# Power_3_3V_Rev1_1.net
KiCad netlist of a schematic drawn in Altium Designer
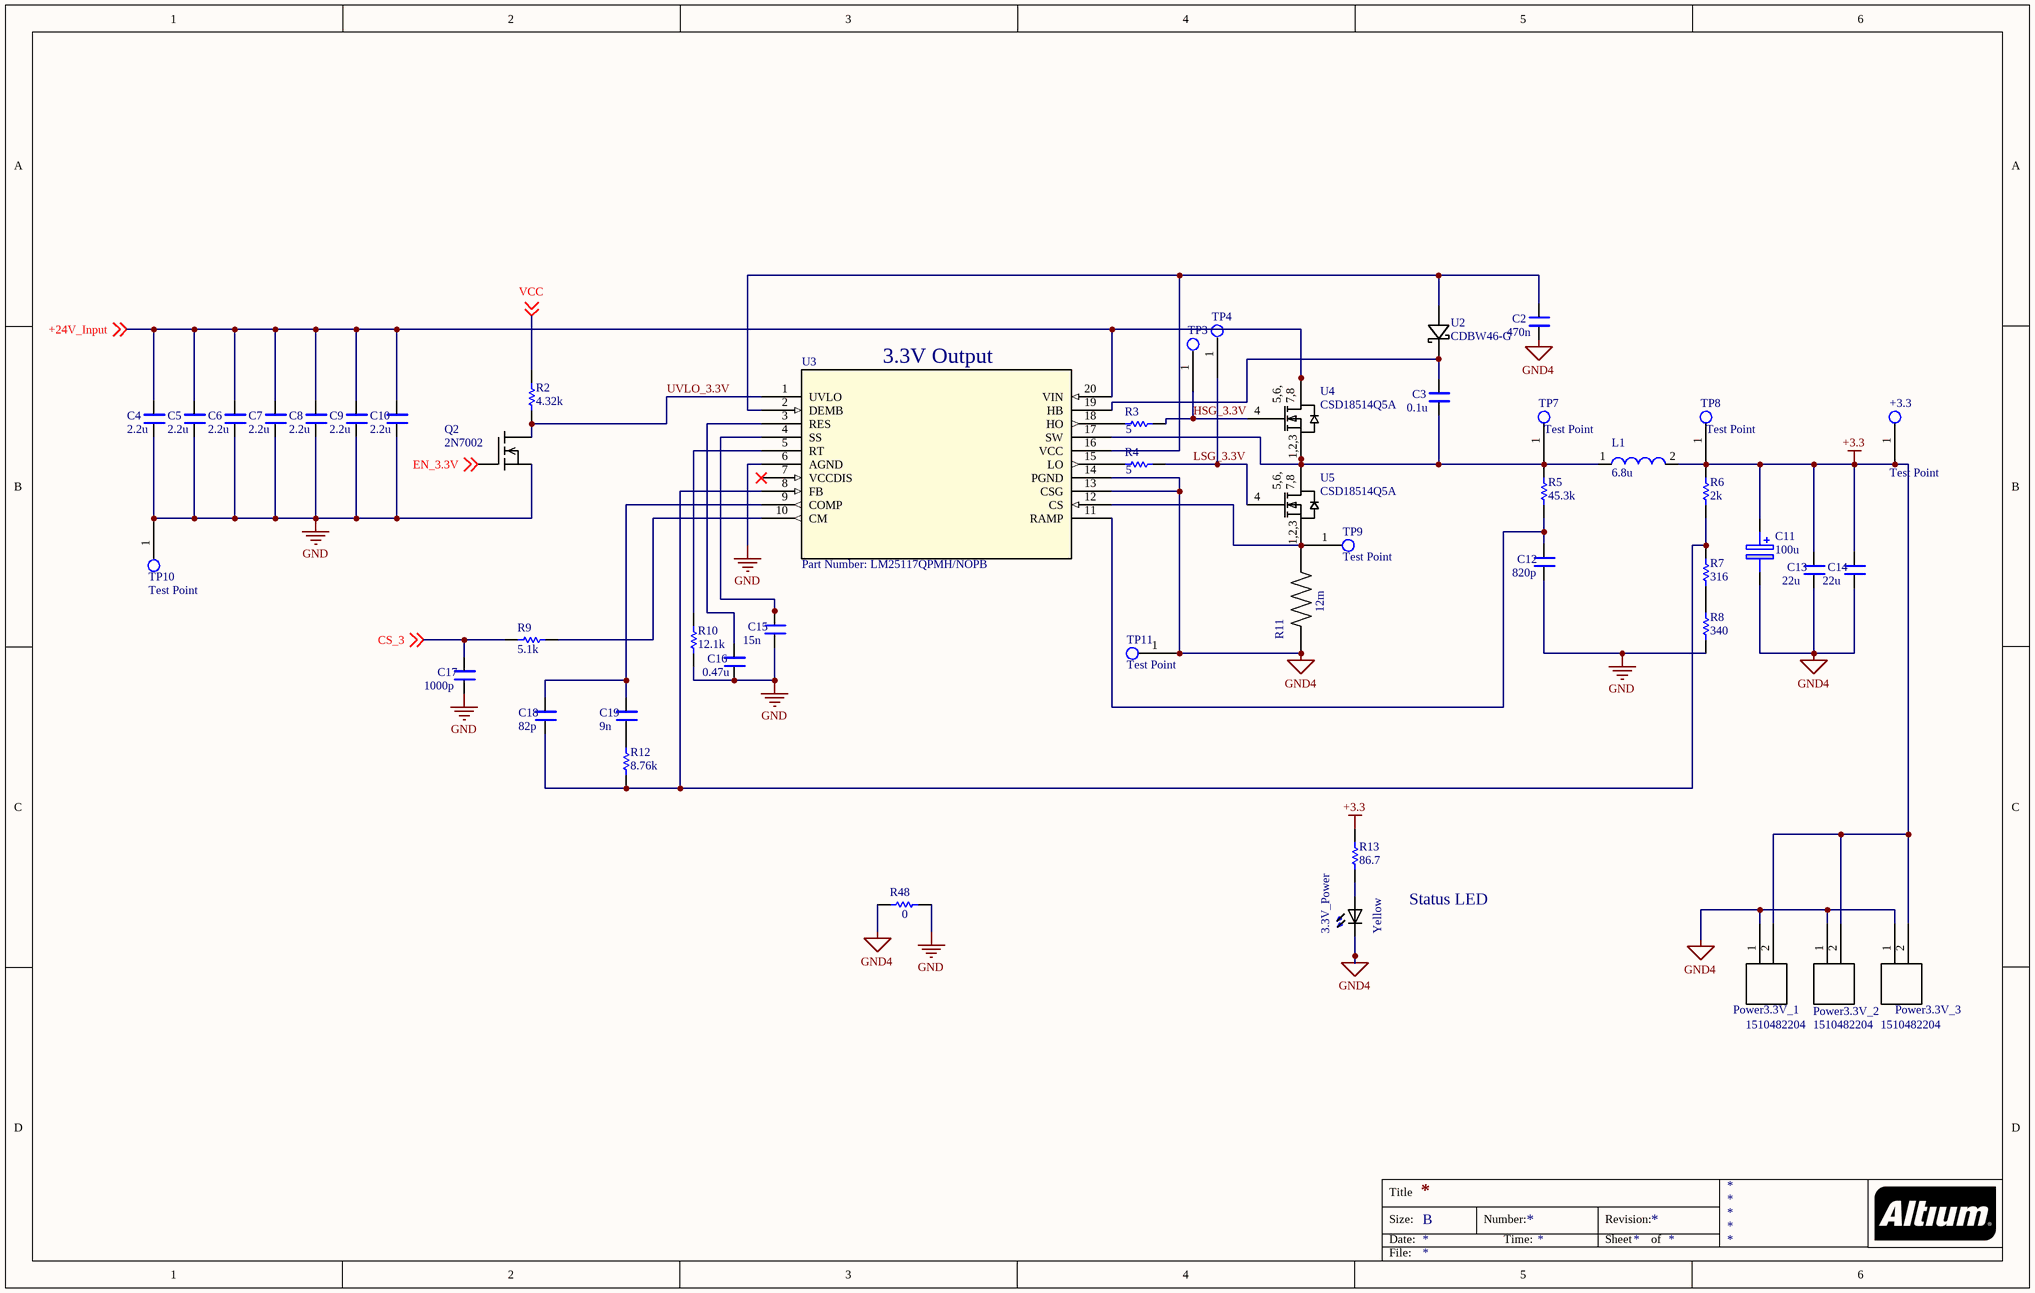
[diagram p0: Power_3.3V_Rev1.1.SchDoc]

(export (version "E")
  (design (tool "Eeschema 10.0.6"))
  (components
    (comp (ref "+3.3")
      (value "Test Point")
      (footprint "Test Point Through-hole")
      (libsource (lib "Test Points") (part "Test Point"))
    )
    (comp (ref "3.3V_Power")
      (value "Yellow")
      (footprint "*DIOC200X125X110_LTST-C171KSKT(Primary)")
      (description "Yellow 2 x 1.25 x 0.8 mm 130Â° Water Clear 50 mcd 2 V LED SMT")
      (fields (field (name "MP") "LTST-C171KSKT") (field (name "DIGI-KEY_PART_NUMBER") "160-1428-1-ND"))
      (libsource (lib "LTST-C171KSKT") (part "LTST-C171KSKT"))
    )
    (comp (ref "C2")
      (value "470n")
      (footprint "*CAPC2012X88N")
      (description "100pF Â±5% 250V Ceramic Capacitor C0G, NP0 0805 _2012 Metric_")
      (fields (field (name "MF") "KEMET") (field (name "DIGI-KEY_PART_NUMBER") "399-15000-1-ND"))
      (libsource (lib "C0805C101JAGAC7800") (part "C0805C101JAGAC7800"))
    )
    (comp (ref "C3")
      (value "0.1u")
      (footprint "*CAPC2012X88N")
      (description "100pF Â±5% 250V Ceramic Capacitor C0G, NP0 0805 _2012 Metric_")
      (fields (field (name "MF") "KEMET") (field (name "DIGI-KEY_PART_NUMBER") "399-15000-1-ND"))
      (libsource (lib "C0805C101JAGAC7800") (part "C0805C101JAGAC7800"))
    )
    (comp (ref "C4")
      (value "2.2u")
      (footprint "*CAPC2012X88N")
      (description "100pF Â±5% 250V Ceramic Capacitor C0G, NP0 0805 _2012 Metric_")
      (fields (field (name "MF") "KEMET") (field (name "DIGI-KEY_PART_NUMBER") "399-15000-1-ND"))
      (libsource (lib "C0805C101JAGAC7800") (part "C0805C101JAGAC7800"))
    )
    (comp (ref "C5")
      (value "2.2u")
      (footprint "*CAPC2012X88N")
      (description "100pF Â±5% 250V Ceramic Capacitor C0G, NP0 0805 _2012 Metric_")
      (fields (field (name "MF") "KEMET") (field (name "DIGI-KEY_PART_NUMBER") "399-15000-1-ND"))
      (libsource (lib "C0805C101JAGAC7800") (part "C0805C101JAGAC7800"))
    )
    (comp (ref "C6")
      (value "2.2u")
      (footprint "*CAPC2012X88N")
      (description "100pF Â±5% 250V Ceramic Capacitor C0G, NP0 0805 _2012 Metric_")
      (fields (field (name "MF") "KEMET") (field (name "DIGI-KEY_PART_NUMBER") "399-15000-1-ND"))
      (libsource (lib "C0805C101JAGAC7800") (part "C0805C101JAGAC7800"))
    )
    (comp (ref "C7")
      (value "2.2u")
      (footprint "*CAPC2012X88N")
      (description "100pF Â±5% 250V Ceramic Capacitor C0G, NP0 0805 _2012 Metric_")
      (fields (field (name "MF") "KEMET") (field (name "DIGI-KEY_PART_NUMBER") "399-15000-1-ND"))
      (libsource (lib "C0805C101JAGAC7800") (part "C0805C101JAGAC7800"))
    )
    (comp (ref "C8")
      (value "2.2u")
      (footprint "*CAPC2012X88N")
      (description "100pF Â±5% 250V Ceramic Capacitor C0G, NP0 0805 _2012 Metric_")
      (fields (field (name "MF") "KEMET") (field (name "DIGI-KEY_PART_NUMBER") "399-15000-1-ND"))
      (libsource (lib "C0805C101JAGAC7800") (part "C0805C101JAGAC7800"))
    )
    (comp (ref "C9")
      (value "2.2u")
      (footprint "*CAPC2012X88N")
      (description "100pF Â±5% 250V Ceramic Capacitor C0G, NP0 0805 _2012 Metric_")
      (fields (field (name "MF") "KEMET") (field (name "DIGI-KEY_PART_NUMBER") "399-15000-1-ND"))
      (libsource (lib "C0805C101JAGAC7800") (part "C0805C101JAGAC7800"))
    )
    (comp (ref "C10")
      (value "2.2u")
      (footprint "*CAPC2012X88N")
      (description "100pF Â±5% 250V Ceramic Capacitor C0G, NP0 0805 _2012 Metric_")
      (fields (field (name "MF") "KEMET") (field (name "DIGI-KEY_PART_NUMBER") "399-15000-1-ND"))
      (libsource (lib "C0805C101JAGAC7800") (part "C0805C101JAGAC7800"))
    )
    (comp (ref "C11")
      (value "100u")
      (footprint "CAPPRD500W65D1000H1800")
      (fields
        (field (name "MANUFACTURER_PART_NUMBER") "EEUFC1V331")
        (field (name "RS PART NUMBER") "1081337")
      )
      (libsource (lib "Power Distribution") (part "EEUFC1V331"))
    )
    (comp (ref "C12")
      (value "820p")
      (footprint "*CAPC2012X88N")
      (description "100pF Â±5% 250V Ceramic Capacitor C0G, NP0 0805 _2012 Metric_")
      (fields (field (name "MF") "KEMET") (field (name "DIGI-KEY_PART_NUMBER") "399-15000-1-ND"))
      (libsource (lib "C0805C101JAGAC7800") (part "C0805C101JAGAC7800"))
    )
    (comp (ref "C13")
      (value "22u")
      (footprint "*CAPC2012X88N")
      (description "100pF Â±5% 250V Ceramic Capacitor C0G, NP0 0805 _2012 Metric_")
      (fields (field (name "MF") "KEMET") (field (name "DIGI-KEY_PART_NUMBER") "399-15000-1-ND"))
      (libsource (lib "C0805C101JAGAC7800") (part "C0805C101JAGAC7800"))
    )
    (comp (ref "C14")
      (value "22u")
      (footprint "*CAPC2012X88N")
      (description "100pF Â±5% 250V Ceramic Capacitor C0G, NP0 0805 _2012 Metric_")
      (fields (field (name "MF") "KEMET") (field (name "DIGI-KEY_PART_NUMBER") "399-15000-1-ND"))
      (libsource (lib "C0805C101JAGAC7800") (part "C0805C101JAGAC7800"))
    )
    (comp (ref "C15")
      (value "15n")
      (footprint "*CAPC2012X88N")
      (description "100pF Â±5% 250V Ceramic Capacitor C0G, NP0 0805 _2012 Metric_")
      (fields (field (name "MF") "KEMET") (field (name "DIGI-KEY_PART_NUMBER") "399-15000-1-ND"))
      (libsource (lib "C0805C101JAGAC7800") (part "C0805C101JAGAC7800"))
    )
    (comp (ref "C16")
      (value "0.47u")
      (footprint "*CAPC2012X88N")
      (description "100pF Â±5% 250V Ceramic Capacitor C0G, NP0 0805 _2012 Metric_")
      (fields (field (name "MF") "KEMET") (field (name "DIGI-KEY_PART_NUMBER") "399-15000-1-ND"))
      (libsource (lib "C0805C101JAGAC7800") (part "C0805C101JAGAC7800"))
    )
    (comp (ref "C17")
      (value "1000p")
      (footprint "*CAPC2012X88N")
      (description "100pF Â±5% 250V Ceramic Capacitor C0G, NP0 0805 _2012 Metric_")
      (fields (field (name "MF") "KEMET") (field (name "DIGI-KEY_PART_NUMBER") "399-15000-1-ND"))
      (libsource (lib "C0805C101JAGAC7800") (part "C0805C101JAGAC7800"))
    )
    (comp (ref "C18")
      (value "82p")
      (footprint "*CAPC2012X88N")
      (description "100pF Â±5% 250V Ceramic Capacitor C0G, NP0 0805 _2012 Metric_")
      (fields (field (name "MF") "KEMET") (field (name "DIGI-KEY_PART_NUMBER") "399-15000-1-ND"))
      (libsource (lib "C0805C101JAGAC7800") (part "C0805C101JAGAC7800"))
    )
    (comp (ref "C19")
      (value "9n")
      (footprint "*CAPC2012X88N")
      (description "100pF Â±5% 250V Ceramic Capacitor C0G, NP0 0805 _2012 Metric_")
      (fields (field (name "MF") "KEMET") (field (name "DIGI-KEY_PART_NUMBER") "399-15000-1-ND"))
      (libsource (lib "C0805C101JAGAC7800") (part "C0805C101JAGAC7800"))
    )
    (comp (ref "L1")
      (value "6.8u")
      (footprint "XAL1010-682")
      (description "Power inductor, high current, 10% tol, SMT, RoHS")
      (fields (field (name "MF") "Coilcraft") (field (name "MP") "SER2915H-153KL"))
      (libsource (lib "SER2915H-153KL") (part "SER2915H-153KL"))
    )
    (comp (ref "Power3.3V_1")
      (value "1510482204")
      (footprint "1510482204")
      (description "Molex 6.5MM 2 pin connector, used for power connections. P/N 1510482204 and similar models.")
      (libsource (lib "Power Distribution") (part "1510482204"))
    )
    (comp (ref "Power3.3V_2")
      (value "1510482204")
      (footprint "1510482204")
      (description "Molex 6.5MM 2 pin connector, used for power connections. P/N 1510482204 and similar models.")
      (libsource (lib "Power Distribution") (part "1510482204"))
    )
    (comp (ref "Power3.3V_3")
      (value "1510482204")
      (footprint "1510482204")
      (description "Molex 6.5MM 2 pin connector, used for power connections. P/N 1510482204 and similar models.")
      (libsource (lib "Power Distribution") (part "1510482204"))
    )
    (comp (ref "Q2")
      (value "2N7002")
      (footprint "*SOT23")
      (description "Trans MOSFET N-CH 60V 0.115A 3-Pin SOT-23 T/R")
      (fields (field (name "MF") "ON Semiconductor"))
      (libsource (lib "2N7002") (part "2N7002"))
    )
    (comp (ref "R2")
      (value "4.32k")
      (footprint "RESC0805(2012)_M")
      (description "8M06 0.125W 1% 0805 (2012 Metric)  SMD")
      (fields (field (name "POWER") "0.125 W") (field (name "TOLERANCE") "1 %"))
      (libsource (lib "Altium Content Vault") (part "RES"))
    )
    (comp (ref "R3")
      (value "5")
      (footprint "AXIAL-0.3")
      (description "120R 0.125W 5% 0805 (2012 Metric)  SMD")
      (fields (field (name "TOLERANCE") "5 %") (field (name "POWER") "0.125 W"))
      (libsource (lib "Power Distribution") (part "120R 5% 0805"))
    )
    (comp (ref "R4")
      (value "5")
      (footprint "AXIAL-0.3")
      (description "120R 0.125W 5% 0805 (2012 Metric)  SMD")
      (fields (field (name "TOLERANCE") "5 %") (field (name "POWER") "0.125 W"))
      (libsource (lib "Power Distribution") (part "120R 5% 0805"))
    )
    (comp (ref "R5")
      (value "45.3k")
      (footprint "RESC0805(2012)_M")
      (description "8M06 0.125W 1% 0805 (2012 Metric)  SMD")
      (fields (field (name "POWER") "0.125 W") (field (name "TOLERANCE") "1 %"))
      (libsource (lib "Altium Content Vault") (part "RES"))
    )
    (comp (ref "R6")
      (value "2k")
      (footprint "RESC0805(2012)_M")
      (description "8M06 0.125W 1% 0805 (2012 Metric)  SMD")
      (fields (field (name "POWER") "0.125 W") (field (name "TOLERANCE") "1 %"))
      (libsource (lib "Altium Content Vault") (part "RES"))
    )
    (comp (ref "R7")
      (value "316")
      (footprint "RESC0805(2012)_M")
      (description "8M06 0.125W 1% 0805 (2012 Metric)  SMD")
      (fields (field (name "POWER") "0.125 W") (field (name "TOLERANCE") "1 %"))
      (libsource (lib "Altium Content Vault") (part "RES"))
    )
    (comp (ref "R8")
      (value "340")
      (footprint "RESC0805(2012)_M")
      (description "8M06 0.125W 1% 0805 (2012 Metric)  SMD")
      (fields (field (name "POWER") "0.125 W") (field (name "TOLERANCE") "1 %"))
      (libsource (lib "Altium Content Vault") (part "RES"))
    )
    (comp (ref "R9")
      (value "5.1k")
      (footprint "RESC0805(2012)_M")
      (description "8M06 0.125W 1% 0805 (2012 Metric)  SMD")
      (fields (field (name "POWER") "0.125 W") (field (name "TOLERANCE") "1 %"))
      (libsource (lib "Altium Content Vault") (part "RES"))
    )
    (comp (ref "R10")
      (value "12.1k")
      (footprint "RESC0805(2012)_M")
      (description "8M06 0.125W 1% 0805 (2012 Metric)  SMD")
      (fields (field (name "POWER") "0.125 W") (field (name "TOLERANCE") "1 %"))
      (libsource (lib "Altium Content Vault") (part "RES"))
    )
    (comp (ref "R11")
      (value "12m")
      (footprint "*RESC6432X110N")
      (description "Res Thick Film 2512 0.012 Ohm 1% 1W Pad SMD Automotive T/R")
      (fields (field (name "MP") "ERJ-M1WSF12MU") (field (name "DIGI-KEY_PART_NUMBER") "P12MCT-ND"))
      (libsource (lib "ERJ-M1WSF12MU") (part "ERJ-M1WSF12MU"))
    )
    (comp (ref "R12")
      (value "8.76k")
      (footprint "RESC0805(2012)_M")
      (description "8M06 0.125W 1% 0805 (2012 Metric)  SMD")
      (fields (field (name "POWER") "0.125 W") (field (name "TOLERANCE") "1 %"))
      (libsource (lib "Altium Content Vault") (part "RES"))
    )
    (comp (ref "R13")
      (value "86.7")
      (footprint "RESC0805(2012)_M")
      (description "8M06 0.125W 1% 0805 (2012 Metric)  SMD")
      (fields (field (name "POWER") "0.125 W") (field (name "TOLERANCE") "1 %"))
      (libsource (lib "Altium Content Vault") (part "RES"))
    )
    (comp (ref "R48")
      (value "0")
      (footprint "RESC0805(2012)_M")
      (description "8M06 0.125W 1% 0805 (2012 Metric)  SMD")
      (fields (field (name "POWER") "0.125 W") (field (name "TOLERANCE") "1 %"))
      (libsource (lib "Altium Content Vault") (part "RES"))
    )
    (comp (ref "TP3")
      (value "~")
      (footprint "Test Point Through-hole")
      (libsource (lib "Test Points") (part "Test Point"))
    )
    (comp (ref "TP4")
      (value "~")
      (footprint "Test Point Through-hole")
      (libsource (lib "Test Points") (part "Test Point"))
    )
    (comp (ref "TP7")
      (value "Test Point")
      (footprint "Test Point Through-hole")
      (libsource (lib "Test Points") (part "Test Point"))
    )
    (comp (ref "TP8")
      (value "Test Point")
      (footprint "Test Point Through-hole")
      (libsource (lib "Test Points") (part "Test Point"))
    )
    (comp (ref "TP9")
      (value "Test Point")
      (footprint "Test Point Through-hole")
      (libsource (lib "Test Points") (part "Test Point"))
    )
    (comp (ref "TP10")
      (value "Test Point")
      (footprint "Test Point Through-hole")
      (libsource (lib "Test Points") (part "Test Point"))
    )
    (comp (ref "TP11")
      (value "Test Point")
      (footprint "Test Point Through-hole")
      (libsource (lib "Test Points") (part "Test Point"))
    )
    (comp (ref "U2")
      (value "CDBW46-G")
      (footprint "CDBW")
      (description "No Description Available")
      (fields (field (name "COPYRIGHT") "Copyright (C) 2018 Accelerated Designs. All rights reserved"))
      (libsource (lib "DIODE SCHOTTKY 100V 150MA") (part "CDBW46-G"))
    )
    (comp (ref "U3")
      (value "Part Number: LM25117QPMH/NOPB")
      (footprint "MXA20A")
      (description "No Description Available")
      (fields
        (field (name "MANUFACTURER") "Texas Instruments")
        (field (name "MANUFACTURER_PART_NUMBER") "LM25117QPMH/NOPB")
        (field (name "COPYRIGHT") "Copyright (C) 2018 Accelerated Designs. All rights reserved")
      )
      (libsource (lib "2019-11-16_22-35-15") (part "LM25117QPMH/NOPB"))
    )
    (comp (ref "U4")
      (value "CSD18514Q5A")
      (footprint "DQJ0008A")
      (description "No Description Available")
      (fields (field (name "COPYRIGHT") "Copyright (C) 2018 Accelerated Designs. All rights reserved"))
      (libsource (lib "ul_CSD18514Q5A") (part "CSD18514Q5A"))
    )
    (comp (ref "U5")
      (value "CSD18514Q5A")
      (footprint "DQJ0008A")
      (description "No Description Available")
      (fields (field (name "COPYRIGHT") "Copyright (C) 2018 Accelerated Designs. All rights reserved"))
      (libsource (lib "ul_CSD18514Q5A") (part "CSD18514Q5A"))
    )
  )
  (nets
    (net (code "1") (name "+3.3") (class "Default")
      (node (ref "+3.3") (pin "1") (pinfunction "1_1") (pintype "passive"))
      (node (ref "C11") (pin "1") (pinfunction "+_1") (pintype "passive"))
      (node (ref "C13") (pin "2") (pinfunction "2_2") (pintype "passive"))
      (node (ref "C14") (pin "2") (pinfunction "2_2") (pintype "passive"))
      (node (ref "L1") (pin "2") (pinfunction "2_2") (pintype "passive"))
      (node (ref "Power3.3V_1") (pin "2") (pintype "passive"))
      (node (ref "Power3.3V_2") (pin "2") (pintype "passive"))
      (node (ref "Power3.3V_3") (pin "2") (pintype "passive"))
      (node (ref "R13") (pin "2") (pinfunction "2_2") (pintype "passive"))
      (node (ref "R6") (pin "2") (pinfunction "2_2") (pintype "passive"))
      (node (ref "TP8") (pin "1") (pinfunction "1_1") (pintype "passive"))
    )
    (net (code "2") (name "+24V_Input") (class "Default")
      (node (ref "C10") (pin "2") (pinfunction "2_2") (pintype "passive"))
      (node (ref "C4") (pin "2") (pinfunction "2_2") (pintype "passive"))
      (node (ref "C5") (pin "2") (pinfunction "2_2") (pintype "passive"))
      (node (ref "C6") (pin "2") (pinfunction "2_2") (pintype "passive"))
      (node (ref "C7") (pin "2") (pinfunction "2_2") (pintype "passive"))
      (node (ref "C8") (pin "2") (pinfunction "2_2") (pintype "passive"))
      (node (ref "C9") (pin "2") (pinfunction "2_2") (pintype "passive"))
      (node (ref "U3") (pin "20") (pinfunction "VIN_20") (pintype "input"))
      (node (ref "U4") (pin "5") (pinfunction "D_5") (pintype "passive"))
      (node (ref "U4") (pin "6") (pinfunction "D_6") (pintype "passive"))
      (node (ref "U4") (pin "7") (pinfunction "D_7") (pintype "passive"))
      (node (ref "U4") (pin "8") (pinfunction "D_8") (pintype "passive"))
    )
    (net (code "3") (name "/HSG_3.3V") (class "Default")
      (node (ref "R3") (pin "2") (pinfunction "2_2") (pintype "passive"))
      (node (ref "TP3") (pin "1") (pinfunction "1_1") (pintype "passive"))
      (node (ref "U4") (pin "4") (pinfunction "G_4") (pintype "passive"))
    )
    (net (code "4") (name "/LSG_3.3V") (class "Default")
      (node (ref "R4") (pin "2") (pinfunction "2_2") (pintype "passive"))
      (node (ref "TP4") (pin "1") (pinfunction "1_1") (pintype "passive"))
      (node (ref "U5") (pin "4") (pinfunction "G_4") (pintype "passive"))
    )
    (net (code "5") (name "/UVLO_3.3V") (class "Default")
      (node (ref "Q2") (pin "3") (pinfunction "D_3") (pintype "passive"))
      (node (ref "R2") (pin "1") (pinfunction "1_1") (pintype "passive"))
      (node (ref "U3") (pin "1") (pinfunction "UVLO_1") (pintype "passive"))
    )
    (net (code "6") (name "CS_3") (class "Default")
      (node (ref "C17") (pin "2") (pinfunction "2_2") (pintype "passive"))
      (node (ref "R9") (pin "2") (pinfunction "2_2") (pintype "passive"))
    )
    (net (code "7") (name "EN_3.3V") (class "Default")
      (node (ref "Q2") (pin "1") (pinfunction "G_1") (pintype "passive"))
    )
    (net (code "8") (name "GND") (class "Default")
      (node (ref "C10") (pin "1") (pinfunction "1_1") (pintype "passive"))
      (node (ref "C12") (pin "1") (pinfunction "1_1") (pintype "passive"))
      (node (ref "C15") (pin "1") (pinfunction "1_1") (pintype "passive"))
      (node (ref "C16") (pin "1") (pinfunction "1_1") (pintype "passive"))
      (node (ref "C17") (pin "1") (pinfunction "1_1") (pintype "passive"))
      (node (ref "C4") (pin "1") (pinfunction "1_1") (pintype "passive"))
      (node (ref "C5") (pin "1") (pinfunction "1_1") (pintype "passive"))
      (node (ref "C6") (pin "1") (pinfunction "1_1") (pintype "passive"))
      (node (ref "C7") (pin "1") (pinfunction "1_1") (pintype "passive"))
      (node (ref "C8") (pin "1") (pinfunction "1_1") (pintype "passive"))
      (node (ref "C9") (pin "1") (pinfunction "1_1") (pintype "passive"))
      (node (ref "Q2") (pin "2") (pinfunction "S_2") (pintype "passive"))
      (node (ref "R10") (pin "1") (pinfunction "1_1") (pintype "passive"))
      (node (ref "R48") (pin "1") (pinfunction "1_1") (pintype "passive"))
      (node (ref "R8") (pin "1") (pinfunction "1_1") (pintype "passive"))
      (node (ref "TP10") (pin "1") (pinfunction "1_1") (pintype "passive"))
      (node (ref "U3") (pin "6") (pinfunction "AGND_6") (pintype "power_in"))
    )
    (net (code "9") (name "GND4") (class "Default")
      (node (ref "3.3V_Power") (pin "NEG") (pinfunction "NEG_NEG") (pintype "passive"))
      (node (ref "C11") (pin "2") (pinfunction "-_2") (pintype "passive"))
      (node (ref "C13") (pin "1") (pinfunction "1_1") (pintype "passive"))
      (node (ref "C14") (pin "1") (pinfunction "1_1") (pintype "passive"))
      (node (ref "C2") (pin "1") (pinfunction "1_1") (pintype "passive"))
      (node (ref "Power3.3V_1") (pin "1") (pintype "passive"))
      (node (ref "Power3.3V_2") (pin "1") (pintype "passive"))
      (node (ref "Power3.3V_3") (pin "1") (pintype "passive"))
      (node (ref "R11") (pin "1") (pinfunction "1_1") (pintype "passive"))
      (node (ref "R48") (pin "2") (pinfunction "2_2") (pintype "passive"))
      (node (ref "TP11") (pin "1") (pinfunction "1_1") (pintype "passive"))
      (node (ref "U3") (pin "13") (pinfunction "CSG_13") (pintype "passive"))
      (node (ref "U3") (pin "14") (pinfunction "PGND_14") (pintype "power_in"))
    )
    (net (code "10") (name "Net-(3.3V_Power-PadPOS)") (class "Default")
      (node (ref "3.3V_Power") (pin "POS") (pinfunction "POS_POS") (pintype "passive"))
      (node (ref "R13") (pin "1") (pinfunction "1_1") (pintype "passive"))
    )
    (net (code "11") (name "Net-(C19-Pad1)") (class "Default")
      (node (ref "C19") (pin "1") (pinfunction "1_1") (pintype "passive"))
      (node (ref "R12") (pin "2") (pinfunction "2_2") (pintype "passive"))
    )
    (net (code "12") (name "Net-(R7-Pad1)") (class "Default")
      (node (ref "R7") (pin "1") (pinfunction "1_1") (pintype "passive"))
      (node (ref "R8") (pin "2") (pinfunction "2_2") (pintype "passive"))
    )
    (net (code "13") (name "Net-(U3-CM)") (class "Default")
      (node (ref "R9") (pin "1") (pinfunction "1_1") (pintype "passive"))
      (node (ref "U3") (pin "10") (pinfunction "CM_10") (pintype "output"))
    )
    (net (code "14") (name "Net-(U3-COMP)") (class "Default")
      (node (ref "C18") (pin "2") (pinfunction "2_2") (pintype "passive"))
      (node (ref "C19") (pin "2") (pinfunction "2_2") (pintype "passive"))
      (node (ref "U3") (pin "9") (pinfunction "COMP_9") (pintype "output"))
    )
    (net (code "15") (name "Net-(U3-CS)") (class "Default")
      (node (ref "R11") (pin "2") (pinfunction "2_2") (pintype "passive"))
      (node (ref "TP9") (pin "1") (pinfunction "1_1") (pintype "passive"))
      (node (ref "U3") (pin "12") (pinfunction "CS_12") (pintype "input"))
      (node (ref "U5") (pin "1") (pinfunction "S_1") (pintype "passive"))
      (node (ref "U5") (pin "2") (pinfunction "S_2") (pintype "passive"))
      (node (ref "U5") (pin "3") (pinfunction "S_3") (pintype "passive"))
    )
    (net (code "16") (name "Net-(U3-DEMB)") (class "Default")
      (node (ref "C2") (pin "2") (pinfunction "2_2") (pintype "passive"))
      (node (ref "U2") (pin "2") (pinfunction "2_2") (pintype "passive"))
      (node (ref "U3") (pin "16") (pinfunction "VCC_16") (pintype "power_in"))
      (node (ref "U3") (pin "2") (pinfunction "DEMB_2") (pintype "input"))
    )
    (net (code "17") (name "Net-(U3-FB)") (class "Default")
      (node (ref "C18") (pin "1") (pinfunction "1_1") (pintype "passive"))
      (node (ref "R12") (pin "1") (pinfunction "1_1") (pintype "passive"))
      (node (ref "R6") (pin "1") (pinfunction "1_1") (pintype "passive"))
      (node (ref "R7") (pin "2") (pinfunction "2_2") (pintype "passive"))
      (node (ref "U3") (pin "8") (pinfunction "FB_8") (pintype "input"))
    )
    (net (code "18") (name "Net-(U3-HB)") (class "Default")
      (node (ref "C3") (pin "2") (pinfunction "2_2") (pintype "passive"))
      (node (ref "U2") (pin "1") (pinfunction "1_1") (pintype "passive"))
      (node (ref "U3") (pin "19") (pinfunction "HB_19") (pintype "passive"))
    )
    (net (code "19") (name "Net-(U3-HO)") (class "Default")
      (node (ref "R3") (pin "1") (pinfunction "1_1") (pintype "passive"))
      (node (ref "U3") (pin "18") (pinfunction "HO_18") (pintype "output"))
    )
    (net (code "20") (name "Net-(U3-LO)") (class "Default")
      (node (ref "R4") (pin "1") (pinfunction "1_1") (pintype "passive"))
      (node (ref "U3") (pin "15") (pinfunction "LO_15") (pintype "output"))
    )
    (net (code "21") (name "Net-(U3-RAMP)") (class "Default")
      (node (ref "C12") (pin "2") (pinfunction "2_2") (pintype "passive"))
      (node (ref "R5") (pin "1") (pinfunction "1_1") (pintype "passive"))
      (node (ref "U3") (pin "11") (pinfunction "RAMP_11") (pintype "passive"))
    )
    (net (code "22") (name "Net-(U3-RES)") (class "Default")
      (node (ref "C16") (pin "2") (pinfunction "2_2") (pintype "passive"))
      (node (ref "U3") (pin "3") (pinfunction "RES_3") (pintype "passive"))
    )
    (net (code "23") (name "Net-(U3-RT)") (class "Default")
      (node (ref "R10") (pin "2") (pinfunction "2_2") (pintype "passive"))
      (node (ref "U3") (pin "5") (pinfunction "RT_5") (pintype "passive"))
    )
    (net (code "24") (name "Net-(U3-SS)") (class "Default")
      (node (ref "C15") (pin "2") (pinfunction "2_2") (pintype "passive"))
      (node (ref "U3") (pin "4") (pinfunction "SS_4") (pintype "passive"))
    )
    (net (code "25") (name "Net-(U3-SW)") (class "Default")
      (node (ref "C3") (pin "1") (pinfunction "1_1") (pintype "passive"))
      (node (ref "L1") (pin "1") (pinfunction "1_1") (pintype "passive"))
      (node (ref "R5") (pin "2") (pinfunction "2_2") (pintype "passive"))
      (node (ref "TP7") (pin "1") (pinfunction "1_1") (pintype "passive"))
      (node (ref "U3") (pin "17") (pinfunction "SW_17") (pintype "passive"))
      (node (ref "U4") (pin "1") (pinfunction "S_1") (pintype "passive"))
      (node (ref "U4") (pin "2") (pinfunction "S_2") (pintype "passive"))
      (node (ref "U4") (pin "3") (pinfunction "S_3") (pintype "passive"))
      (node (ref "U5") (pin "5") (pinfunction "D_5") (pintype "passive"))
      (node (ref "U5") (pin "6") (pinfunction "D_6") (pintype "passive"))
      (node (ref "U5") (pin "7") (pinfunction "D_7") (pintype "passive"))
      (node (ref "U5") (pin "8") (pinfunction "D_8") (pintype "passive"))
    )
    (net (code "26") (name "VCC") (class "Default")
      (node (ref "R2") (pin "2") (pinfunction "2_2") (pintype "passive"))
    )
    (net (code "27") (name "unconnected-(U3-VCCDIS-Pad7)") (class "Default")
      (node (ref "U3") (pin "7") (pinfunction "VCCDIS_7") (pintype "input+no_connect"))
    )
  )
)
